# POWER.net
KiCad netlist of a schematic drawn in Altium Designer
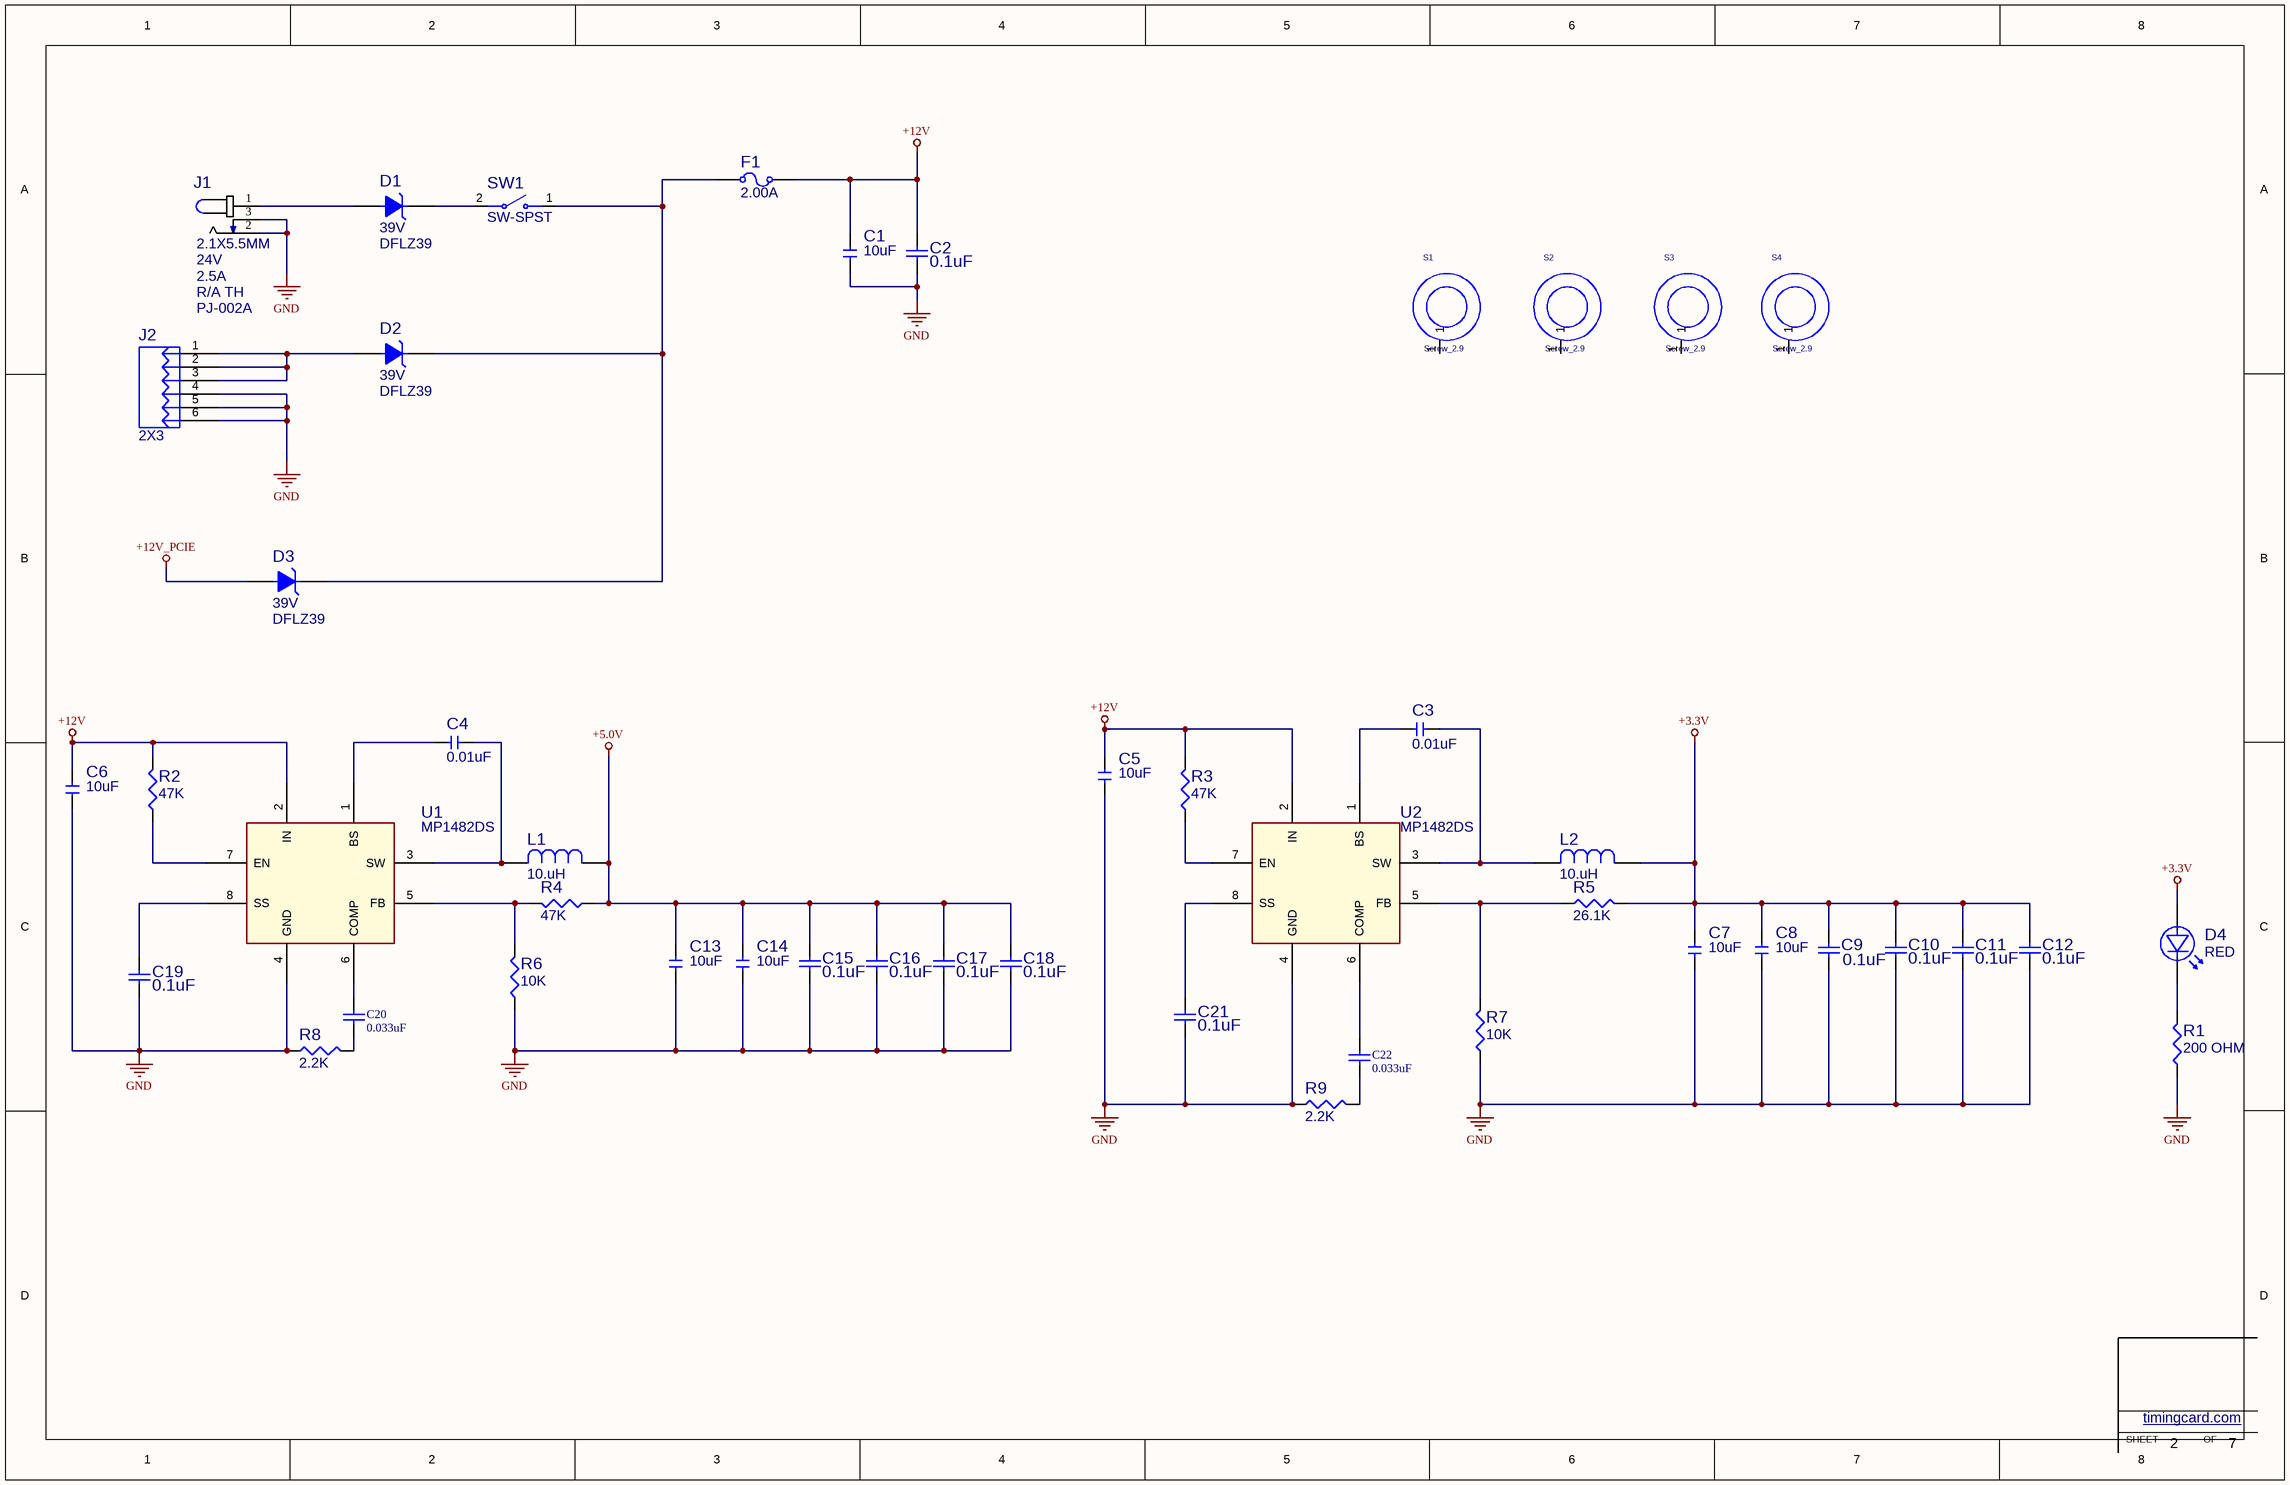
[diagram p0: POWER.SchDoc]

(export (version "E")
  (design (tool "Eeschema 10.0.6"))
  (components
    (comp (ref "C1")
      (value "10uF")
      (footprint "CAPC2012X14N")
      (description "CAP, CER, 10.UF, 25V, 10%, X5R, 0805")
      (fields
        (field (name "MFG PART NUM") "TMK212BBJ106KG-T")
        (field (name "VALENTIUM PART NUM") "<VALENTIUM>")
      )
      (libsource (lib "Capacitors") (part "CAP_0805_10UF_25V"))
    )
    (comp (ref "C2")
      (value "0.1uF")
      (footprint "CAPC1608X87X45ML20T05")
      (description "C0603X104K5RACAUTO")
      (fields (field (name "MANUFACTURER") "Kemet"))
      (libsource (lib "Altium Content Vault") (part "CAP"))
    )
    (comp (ref "C3")
      (value "0.01uF")
      (footprint "CAPC1608X10N")
      (description "CAP, CER, 0.01UF, 50V, 10%, X7R, 0603")
      (fields
        (field (name "MFG PART NUM") "C0603C103K5RACTU")
        (field (name "VALENTIUM PART NUM") "<VALENTIUM>")
      )
      (libsource (lib "Capacitors") (part "CAP_0603_0.01UF_50V"))
    )
    (comp (ref "C4")
      (value "0.01uF")
      (footprint "CAPC1608X10N")
      (description "CAP, CER, 0.01UF, 50V, 10%, X7R, 0603")
      (fields
        (field (name "MFG PART NUM") "C0603C103K5RACTU")
        (field (name "VALENTIUM PART NUM") "<VALENTIUM>")
      )
      (libsource (lib "Capacitors") (part "CAP_0603_0.01UF_50V"))
    )
    (comp (ref "C5")
      (value "10uF")
      (footprint "CAPC2012X14N")
      (description "CAP, CER, 10.UF, 25V, 10%, X5R, 0805")
      (fields
        (field (name "MFG PART NUM") "TMK212BBJ106KG-T")
        (field (name "VALENTIUM PART NUM") "<VALENTIUM>")
      )
      (libsource (lib "Capacitors") (part "CAP_0805_10UF_25V"))
    )
    (comp (ref "C6")
      (value "10uF")
      (footprint "CAPC2012X14N")
      (description "CAP, CER, 10.UF, 25V, 10%, X5R, 0805")
      (fields
        (field (name "MFG PART NUM") "TMK212BBJ106KG-T")
        (field (name "VALENTIUM PART NUM") "<VALENTIUM>")
      )
      (libsource (lib "Capacitors") (part "CAP_0805_10UF_25V"))
    )
    (comp (ref "C7")
      (value "10uF")
      (footprint "CAPC2012X14N")
      (description "CAP, CER, 10.UF, 25V, 10%, X5R, 0805")
      (fields
        (field (name "MFG PART NUM") "TMK212BBJ106KG-T")
        (field (name "VALENTIUM PART NUM") "<VALENTIUM>")
      )
      (libsource (lib "Capacitors") (part "CAP_0805_10UF_25V"))
    )
    (comp (ref "C8")
      (value "10uF")
      (footprint "CAPC2012X14N")
      (description "CAP, CER, 10.UF, 25V, 10%, X5R, 0805")
      (fields
        (field (name "MFG PART NUM") "TMK212BBJ106KG-T")
        (field (name "VALENTIUM PART NUM") "<VALENTIUM>")
      )
      (libsource (lib "Capacitors") (part "CAP_0805_10UF_25V"))
    )
    (comp (ref "C9")
      (value "0.1uF")
      (footprint "CAPC1608X87X45ML20T05")
      (description "C0603X104K5RACAUTO")
      (fields (field (name "MANUFACTURER") "Kemet"))
      (libsource (lib "Altium Content Vault") (part "CAP"))
    )
    (comp (ref "C10")
      (value "0.1uF")
      (footprint "CAPC1608X87X45ML20T05")
      (description "C0603X104K5RACAUTO")
      (fields (field (name "MANUFACTURER") "Kemet"))
      (libsource (lib "Altium Content Vault") (part "CAP"))
    )
    (comp (ref "C11")
      (value "0.1uF")
      (footprint "CAPC1608X87X45ML20T05")
      (description "C0603X104K5RACAUTO")
      (fields (field (name "MANUFACTURER") "Kemet"))
      (libsource (lib "Altium Content Vault") (part "CAP"))
    )
    (comp (ref "C12")
      (value "0.1uF")
      (footprint "CAPC1608X87X45ML20T05")
      (description "C0603X104K5RACAUTO")
      (fields (field (name "MANUFACTURER") "Kemet"))
      (libsource (lib "Altium Content Vault") (part "CAP"))
    )
    (comp (ref "C13")
      (value "10uF")
      (footprint "CAPC2012X14N")
      (description "CAP, CER, 10.UF, 25V, 10%, X5R, 0805")
      (fields
        (field (name "MFG PART NUM") "TMK212BBJ106KG-T")
        (field (name "VALENTIUM PART NUM") "<VALENTIUM>")
      )
      (libsource (lib "Capacitors") (part "CAP_0805_10UF_25V"))
    )
    (comp (ref "C14")
      (value "10uF")
      (footprint "CAPC2012X14N")
      (description "CAP, CER, 10.UF, 25V, 10%, X5R, 0805")
      (fields
        (field (name "MFG PART NUM") "TMK212BBJ106KG-T")
        (field (name "VALENTIUM PART NUM") "<VALENTIUM>")
      )
      (libsource (lib "Capacitors") (part "CAP_0805_10UF_25V"))
    )
    (comp (ref "C15")
      (value "0.1uF")
      (footprint "CAPC1608X87X45ML20T05")
      (description "C0603X104K5RACAUTO")
      (fields (field (name "MANUFACTURER") "Kemet"))
      (libsource (lib "Altium Content Vault") (part "CAP"))
    )
    (comp (ref "C16")
      (value "0.1uF")
      (footprint "CAPC1608X87X45ML20T05")
      (description "C0603X104K5RACAUTO")
      (fields (field (name "MANUFACTURER") "Kemet"))
      (libsource (lib "Altium Content Vault") (part "CAP"))
    )
    (comp (ref "C17")
      (value "0.1uF")
      (footprint "CAPC1608X87X45ML20T05")
      (description "C0603X104K5RACAUTO")
      (fields (field (name "MANUFACTURER") "Kemet"))
      (libsource (lib "Altium Content Vault") (part "CAP"))
    )
    (comp (ref "C18")
      (value "0.1uF")
      (footprint "CAPC1608X87X45ML20T05")
      (description "C0603X104K5RACAUTO")
      (fields (field (name "MANUFACTURER") "Kemet"))
      (libsource (lib "Altium Content Vault") (part "CAP"))
    )
    (comp (ref "C19")
      (value "0.1uF")
      (footprint "CAPC1608X87X45ML20T05")
      (description "C0603X104K5RACAUTO")
      (fields (field (name "MANUFACTURER") "Kemet"))
      (libsource (lib "Altium Content Vault") (part "CAP"))
    )
    (comp (ref "C20")
      (value "0.033uF")
      (footprint "CAPC1608X90X35NL10T15")
      (description "GCM188R71H333KA55D")
      (fields (field (name "MANUFACTURER") "Murata"))
      (libsource (lib "Altium Content Vault") (part "CAP"))
    )
    (comp (ref "C21")
      (value "0.1uF")
      (footprint "CAPC1608X87X45ML20T05")
      (description "C0603X104K5RACAUTO")
      (fields (field (name "MANUFACTURER") "Kemet"))
      (libsource (lib "Altium Content Vault") (part "CAP"))
    )
    (comp (ref "C22")
      (value "0.033uF")
      (footprint "CAPC1608X90X35NL10T15")
      (description "GCM188R71H333KA55D")
      (fields (field (name "MANUFACTURER") "Murata"))
      (libsource (lib "Altium Content Vault") (part "CAP"))
    )
    (comp (ref "D1")
      (value "DFLZ39")
      (footprint "SODFL370X135-2N")
      (description "DIO, ZENER, DFLZ39, 39V, 5%, 1W, SOD123FL")
      (fields
        (field (name "MFG PART NUM") "DFLZ39-TP")
        (field (name "P1") "39V")
        (field (name "VALENTIUM PART NUM") "<VALENTIUM>")
      )
      (libsource (lib "Passives") (part "DFLZ39"))
    )
    (comp (ref "D2")
      (value "DFLZ39")
      (footprint "SODFL370X135-2N")
      (description "DIO, ZENER, DFLZ39, 39V, 5%, 1W, SOD123FL")
      (fields
        (field (name "MFG PART NUM") "DFLZ39-TP")
        (field (name "P1") "39V")
        (field (name "VALENTIUM PART NUM") "<VALENTIUM>")
      )
      (libsource (lib "Passives") (part "DFLZ39"))
    )
    (comp (ref "D3")
      (value "DFLZ39")
      (footprint "SODFL370X135-2N")
      (description "DIO, ZENER, DFLZ39, 39V, 5%, 1W, SOD123FL")
      (fields
        (field (name "MFG PART NUM") "DFLZ39-TP")
        (field (name "P1") "39V")
        (field (name "VALENTIUM PART NUM") "<VALENTIUM>")
      )
      (libsource (lib "Passives") (part "DFLZ39"))
    )
    (comp (ref "D4")
      (value "RED")
      (footprint "DIOM1608X06N")
      (description "LED, RED, SML-LX0603, 635NM, 2V, 20MA, 0603")
      (fields
        (field (name "MFG PART NUM") "SML-LX0603IW-TR")
        (field (name "VALENTIUM PART NUM") "<VALENTIUM>")
      )
      (libsource (lib "Passives") (part "SMTLED_RED_0603_SML"))
    )
    (comp (ref "F1")
      (value "2.00A")
      (footprint "FUSM1608X60N")
      (description "FUSE SLOW 2.00A 32V M 0603")
      (fields (field (name "MFG PART NUM") "SF-0603S200-2") (field (name "VALENTIUM PART NUM") "<VALENTIUM>"))
      (libsource (lib "Passives") (part "FUSE_0603_2.00A"))
    )
    (comp (ref "J1")
      (value "PJ-002A")
      (footprint "CUI_PJ-002A")
      (description "CONN, JACK, PJ-002A, 2.1X5.5MM, 24V 2.5A, R/A TH, SPST-NC")
      (fields
        (field (name "VALENTIUM PART NUM") "<VALENTIUM>")
        (field (name "P1") "2.1X5.5MM")
        (field (name "P2") "24V")
        (field (name "P3") "2.5A")
        (field (name "SIZE") "R/A TH")
      )
      (libsource (lib "Connectors") (part "PJ-002A"))
    )
    (comp (ref "J2")
      (value "2X3")
      (footprint "39-30-1060")
      (description "CONN, HDR, 2X3, R/A, 4.2MM, TH, MINI-FIT JR")
      (fields (field (name "MFG PART NUM") "105314-1206") (field (name "VALENTIUM PART NUM") "<VALENTIUM>"))
      (libsource (lib "Connectors") (part "39-30-1060"))
    )
    (comp (ref "L1")
      (value "10.uH")
      (footprint "IND_PM124SH")
      (description "IND, PWR, 10.uH, 20%, 4A, 0.04DCR, 12.5X12.5MM, SHLD")
      (fields
        (field (name "MFG PART NUM") "PM124SH-100M-RC")
        (field (name "VALENTIUM PART NUM") "<VALENTIUM>")
      )
      (libsource (lib "Passives") (part "PM124SH-100M-RC"))
    )
    (comp (ref "L2")
      (value "10.uH")
      (footprint "IND_PM124SH")
      (description "IND, PWR, 10.uH, 20%, 4A, 0.04DCR, 12.5X12.5MM, SHLD")
      (fields
        (field (name "MFG PART NUM") "PM124SH-100M-RC")
        (field (name "VALENTIUM PART NUM") "<VALENTIUM>")
      )
      (libsource (lib "Passives") (part "PM124SH-100M-RC"))
    )
    (comp (ref "R1")
      (value "200 OHM")
      (footprint "RESC1608X50N")
      (description "RES, 200 OHM, 1%, 1/10W, TF, 0603")
      (fields (field (name "MFG PART NUM") "ERJ-3EKF2000V") (field (name "VELENTIUM PART NUM") "<VELENTIUM>"))
      (libsource (lib "Resistors") (part "RES_0603_200"))
    )
    (comp (ref "R2")
      (value "47K")
      (footprint "RESC1608X50N")
      (description "RES, 47K, 1%, 1/10W, TF, 0603")
      (fields (field (name "MFG PART NUM") "ERJ-3EKF4702V") (field (name "VELENTIUM PART NUM") "<VELENTIUM>"))
      (libsource (lib "Resistors") (part "RES_0603_47K"))
    )
    (comp (ref "R3")
      (value "47K")
      (footprint "RESC1608X50N")
      (description "RES, 47K, 1%, 1/10W, TF, 0603")
      (fields (field (name "MFG PART NUM") "ERJ-3EKF4702V") (field (name "VELENTIUM PART NUM") "<VELENTIUM>"))
      (libsource (lib "Resistors") (part "RES_0603_47K"))
    )
    (comp (ref "R4")
      (value "47K")
      (footprint "RESC1608X50N")
      (description "RES, 47K, 1%, 1/10W, TF, 0603")
      (fields (field (name "MFG PART NUM") "ERJ-3EKF4702V") (field (name "VELENTIUM PART NUM") "<VELENTIUM>"))
      (libsource (lib "Resistors") (part "RES_0603_47K"))
    )
    (comp (ref "R5")
      (value "26.1K")
      (footprint "RESC1608X50N")
      (description "RES, 26.1K, 1%, 1/10W, TF, 0603")
      (fields (field (name "MFG PART NUM") "ERJ-3EKF2612V") (field (name "VELENTIUM PART NUM") "<VELENTIUM>"))
      (libsource (lib "Resistors") (part "RES_0603_26.1K"))
    )
    (comp (ref "R6")
      (value "10K")
      (footprint "RESC1608X50N")
      (description "RES, 10K, 1%, 1/10W, TF, 0603")
      (fields (field (name "MFG PART NUM") "ERJ-3EKF1002V") (field (name "VELENTIUM PART NUM") "<VELENTIUM>"))
      (libsource (lib "Resistors") (part "RES_0603_10K"))
    )
    (comp (ref "R7")
      (value "10K")
      (footprint "RESC1608X50N")
      (description "RES, 10K, 1%, 1/10W, TF, 0603")
      (fields (field (name "MFG PART NUM") "ERJ-3EKF1002V") (field (name "VELENTIUM PART NUM") "<VELENTIUM>"))
      (libsource (lib "Resistors") (part "RES_0603_10K"))
    )
    (comp (ref "R8")
      (value "2.2K")
      (footprint "RESC1608X50N")
      (description "RES, 2.2K, 1%, 1/10W, TF, 0603")
      (fields (field (name "MFG PART NUM") "ERJ-3EKF2201V") (field (name "VELENTIUM PART NUM") "<VELENTIUM>"))
      (libsource (lib "Resistors") (part "RES_0603_2.2K"))
    )
    (comp (ref "R9")
      (value "2.2K")
      (footprint "RESC1608X50N")
      (description "RES, 2.2K, 1%, 1/10W, TF, 0603")
      (fields (field (name "MFG PART NUM") "ERJ-3EKF2201V") (field (name "VELENTIUM PART NUM") "<VELENTIUM>"))
      (libsource (lib "Resistors") (part "RES_0603_2.2K"))
    )
    (comp (ref "S1")
      (value "Screw_2.9")
      (footprint "MH_250H125")
      (description "FH140 Screw,Diameter 2.9mm")
      (fields (field (name "PART NUMBER") "454") (field (name "MANUFACTURER") "NA"))
      (libsource (lib "AX7103_AD_Schematics") (part "screw_0"))
    )
    (comp (ref "S2")
      (value "Screw_2.9")
      (footprint "MH_250H125")
      (description "FH140 Screw,Diameter 2.9mm")
      (fields (field (name "PART NUMBER") "454") (field (name "MANUFACTURER") "NA"))
      (libsource (lib "AX7103_AD_Schematics") (part "screw_0"))
    )
    (comp (ref "S3")
      (value "Screw_2.9")
      (footprint "MH_250H125")
      (description "FH140 Screw,Diameter 2.9mm")
      (fields (field (name "PART NUMBER") "454") (field (name "MANUFACTURER") "NA"))
      (libsource (lib "AX7103_AD_Schematics") (part "screw_0"))
    )
    (comp (ref "S4")
      (value "Screw_2.9")
      (footprint "MH_250H125")
      (description "FH140 Screw,Diameter 2.9mm")
      (fields (field (name "PART NUMBER") "454") (field (name "MANUFACTURER") "NA"))
      (libsource (lib "AX7103_AD_Schematics") (part "screw_0"))
    )
    (comp (ref "SW1")
      (value "SW-SPST")
      (footprint "L101011MS02Q")
      (description "SW, SPST, 250V, 2A, SLIDE, ON-OFF, TH")
      (fields (field (name "MFG PART NUM") "L101011MS02Q") (field (name "VALENTIUM PART NUM") "<VALENTIUM>"))
      (libsource (lib "Miscellaneous") (part "L101011MS02Q"))
    )
    (comp (ref "U1")
      (value "MP1482DS")
      (footprint "SOIC127P600X175-8N")
      (description "IC, DC/DC, MP1482DS, >4.75VIN, 0.923-15V OUT, SOIC8")
      (fields (field (name "MFG PART NUM") "MP1482DS-LF") (field (name "VELENTIUM PART NUM") "<V PART NUM>"))
      (libsource (lib "IntegratedCircuits") (part "MP1482DS"))
    )
    (comp (ref "U2")
      (value "MP1482DS")
      (footprint "SOIC127P600X175-8N")
      (description "IC, DC/DC, MP1482DS, >4.75VIN, 0.923-15V OUT, SOIC8")
      (fields (field (name "MFG PART NUM") "MP1482DS-LF") (field (name "VELENTIUM PART NUM") "<V PART NUM>"))
      (libsource (lib "IntegratedCircuits") (part "MP1482DS"))
    )
  )
  (nets
    (net (code "1") (name "+3.3V") (class "Default")
      (node (ref "C10") (pin "2") (pinfunction "2_2") (pintype "passive"))
      (node (ref "C11") (pin "2") (pinfunction "2_2") (pintype "passive"))
      (node (ref "C12") (pin "2") (pinfunction "2_2") (pintype "passive"))
      (node (ref "C7") (pin "1") (pinfunction "1_1") (pintype "passive"))
      (node (ref "C8") (pin "1") (pinfunction "1_1") (pintype "passive"))
      (node (ref "C9") (pin "2") (pinfunction "2_2") (pintype "passive"))
      (node (ref "D4") (pin "2") (pinfunction "A_2") (pintype "passive"))
      (node (ref "L2") (pin "1") (pintype "passive"))
      (node (ref "R5") (pin "2") (pinfunction "2_2") (pintype "passive"))
    )
    (net (code "2") (name "+5.0V") (class "Default")
      (node (ref "C13") (pin "1") (pinfunction "1_1") (pintype "passive"))
      (node (ref "C14") (pin "1") (pinfunction "1_1") (pintype "passive"))
      (node (ref "C15") (pin "2") (pinfunction "2_2") (pintype "passive"))
      (node (ref "C16") (pin "2") (pinfunction "2_2") (pintype "passive"))
      (node (ref "C17") (pin "2") (pinfunction "2_2") (pintype "passive"))
      (node (ref "C18") (pin "2") (pinfunction "2_2") (pintype "passive"))
      (node (ref "L1") (pin "1") (pintype "passive"))
      (node (ref "R4") (pin "1") (pinfunction "1_1") (pintype "passive"))
    )
    (net (code "3") (name "+12V") (class "Default")
      (node (ref "C1") (pin "1") (pinfunction "1_1") (pintype "passive"))
      (node (ref "C2") (pin "2") (pinfunction "2_2") (pintype "passive"))
      (node (ref "C5") (pin "1") (pinfunction "1_1") (pintype "passive"))
      (node (ref "C6") (pin "1") (pinfunction "1_1") (pintype "passive"))
      (node (ref "F1") (pin "2") (pinfunction "2_2") (pintype "passive"))
      (node (ref "R2") (pin "2") (pinfunction "2_2") (pintype "passive"))
      (node (ref "R3") (pin "2") (pinfunction "2_2") (pintype "passive"))
      (node (ref "U1") (pin "2") (pinfunction "IN_2") (pintype "passive"))
      (node (ref "U2") (pin "2") (pinfunction "IN_2") (pintype "passive"))
    )
    (net (code "4") (name "+12V_PCIE") (class "Default")
      (node (ref "D3") (pin "2") (pinfunction "A_2") (pintype "passive"))
    )
    (net (code "5") (name "GND") (class "Default")
      (node (ref "C1") (pin "2") (pinfunction "2_2") (pintype "passive"))
      (node (ref "C10") (pin "1") (pinfunction "1_1") (pintype "passive"))
      (node (ref "C11") (pin "1") (pinfunction "1_1") (pintype "passive"))
      (node (ref "C12") (pin "1") (pinfunction "1_1") (pintype "passive"))
      (node (ref "C13") (pin "2") (pinfunction "2_2") (pintype "passive"))
      (node (ref "C14") (pin "2") (pinfunction "2_2") (pintype "passive"))
      (node (ref "C15") (pin "1") (pinfunction "1_1") (pintype "passive"))
      (node (ref "C16") (pin "1") (pinfunction "1_1") (pintype "passive"))
      (node (ref "C17") (pin "1") (pinfunction "1_1") (pintype "passive"))
      (node (ref "C18") (pin "1") (pinfunction "1_1") (pintype "passive"))
      (node (ref "C19") (pin "1") (pinfunction "1_1") (pintype "passive"))
      (node (ref "C2") (pin "1") (pinfunction "1_1") (pintype "passive"))
      (node (ref "C21") (pin "1") (pinfunction "1_1") (pintype "passive"))
      (node (ref "C5") (pin "2") (pinfunction "2_2") (pintype "passive"))
      (node (ref "C6") (pin "2") (pinfunction "2_2") (pintype "passive"))
      (node (ref "C7") (pin "2") (pinfunction "2_2") (pintype "passive"))
      (node (ref "C8") (pin "2") (pinfunction "2_2") (pintype "passive"))
      (node (ref "C9") (pin "1") (pinfunction "1_1") (pintype "passive"))
      (node (ref "J1") (pin "2") (pinfunction "2_2") (pintype "passive"))
      (node (ref "J1") (pin "3") (pinfunction "3_3") (pintype "passive"))
      (node (ref "J2") (pin "4") (pintype "passive"))
      (node (ref "J2") (pin "5") (pintype "passive"))
      (node (ref "J2") (pin "6") (pintype "passive"))
      (node (ref "R1") (pin "1") (pinfunction "1_1") (pintype "passive"))
      (node (ref "R6") (pin "1") (pinfunction "1_1") (pintype "passive"))
      (node (ref "R7") (pin "1") (pinfunction "1_1") (pintype "passive"))
      (node (ref "R8") (pin "1") (pinfunction "1_1") (pintype "passive"))
      (node (ref "R9") (pin "1") (pinfunction "1_1") (pintype "passive"))
      (node (ref "U1") (pin "4") (pinfunction "GND_4") (pintype "passive"))
      (node (ref "U2") (pin "4") (pinfunction "GND_4") (pintype "passive"))
    )
    (net (code "6") (name "Net-(C20-Pad1)") (class "Default")
      (node (ref "C20") (pin "1") (pinfunction "1_1") (pintype "passive"))
      (node (ref "R8") (pin "2") (pinfunction "2_2") (pintype "passive"))
    )
    (net (code "7") (name "Net-(C22-Pad1)") (class "Default")
      (node (ref "C22") (pin "1") (pinfunction "1_1") (pintype "passive"))
      (node (ref "R9") (pin "2") (pinfunction "2_2") (pintype "passive"))
    )
    (net (code "8") (name "Net-(D1-A)") (class "Default")
      (node (ref "D1") (pin "2") (pinfunction "A_2") (pintype "passive"))
      (node (ref "J1") (pin "1") (pinfunction "1_1") (pintype "passive"))
    )
    (net (code "9") (name "Net-(D1-C)") (class "Default")
      (node (ref "D1") (pin "1") (pinfunction "C_1") (pintype "passive"))
      (node (ref "SW1") (pin "2") (pintype "passive"))
    )
    (net (code "10") (name "Net-(D2-A)") (class "Default")
      (node (ref "D2") (pin "2") (pinfunction "A_2") (pintype "passive"))
      (node (ref "J2") (pin "1") (pintype "passive"))
      (node (ref "J2") (pin "2") (pintype "passive"))
      (node (ref "J2") (pin "3") (pintype "passive"))
    )
    (net (code "11") (name "Net-(D2-C)") (class "Default")
      (node (ref "D2") (pin "1") (pinfunction "C_1") (pintype "passive"))
      (node (ref "D3") (pin "1") (pinfunction "C_1") (pintype "passive"))
      (node (ref "F1") (pin "1") (pinfunction "1_1") (pintype "passive"))
      (node (ref "SW1") (pin "1") (pintype "passive"))
    )
    (net (code "12") (name "Net-(D4-K)") (class "Default")
      (node (ref "D4") (pin "1") (pinfunction "K_1") (pintype "passive"))
      (node (ref "R1") (pin "2") (pinfunction "2_2") (pintype "passive"))
    )
    (net (code "13") (name "Net-(U1-BS)") (class "Default")
      (node (ref "C4") (pin "1") (pinfunction "1_1") (pintype "passive"))
      (node (ref "U1") (pin "1") (pinfunction "BS_1") (pintype "passive"))
    )
    (net (code "14") (name "Net-(U1-COMP)") (class "Default")
      (node (ref "C20") (pin "2") (pinfunction "2_2") (pintype "passive"))
      (node (ref "U1") (pin "6") (pinfunction "COMP_6") (pintype "passive"))
    )
    (net (code "15") (name "Net-(U1-EN)") (class "Default")
      (node (ref "R2") (pin "1") (pinfunction "1_1") (pintype "passive"))
      (node (ref "U1") (pin "7") (pinfunction "EN_7") (pintype "passive"))
    )
    (net (code "16") (name "Net-(U1-FB)") (class "Default")
      (node (ref "R4") (pin "2") (pinfunction "2_2") (pintype "passive"))
      (node (ref "R6") (pin "2") (pinfunction "2_2") (pintype "passive"))
      (node (ref "U1") (pin "5") (pinfunction "FB_5") (pintype "passive"))
    )
    (net (code "17") (name "Net-(U1-SS)") (class "Default")
      (node (ref "C19") (pin "2") (pinfunction "2_2") (pintype "passive"))
      (node (ref "U1") (pin "8") (pinfunction "SS_8") (pintype "passive"))
    )
    (net (code "18") (name "Net-(U1-SW)") (class "Default")
      (node (ref "C4") (pin "2") (pinfunction "2_2") (pintype "passive"))
      (node (ref "L1") (pin "2") (pintype "passive"))
      (node (ref "U1") (pin "3") (pinfunction "SW_3") (pintype "passive"))
    )
    (net (code "19") (name "Net-(U2-BS)") (class "Default")
      (node (ref "C3") (pin "1") (pinfunction "1_1") (pintype "passive"))
      (node (ref "U2") (pin "1") (pinfunction "BS_1") (pintype "passive"))
    )
    (net (code "20") (name "Net-(U2-COMP)") (class "Default")
      (node (ref "C22") (pin "2") (pinfunction "2_2") (pintype "passive"))
      (node (ref "U2") (pin "6") (pinfunction "COMP_6") (pintype "passive"))
    )
    (net (code "21") (name "Net-(U2-EN)") (class "Default")
      (node (ref "R3") (pin "1") (pinfunction "1_1") (pintype "passive"))
      (node (ref "U2") (pin "7") (pinfunction "EN_7") (pintype "passive"))
    )
    (net (code "22") (name "Net-(U2-FB)") (class "Default")
      (node (ref "R5") (pin "1") (pinfunction "1_1") (pintype "passive"))
      (node (ref "R7") (pin "2") (pinfunction "2_2") (pintype "passive"))
      (node (ref "U2") (pin "5") (pinfunction "FB_5") (pintype "passive"))
    )
    (net (code "23") (name "Net-(U2-SS)") (class "Default")
      (node (ref "C21") (pin "2") (pinfunction "2_2") (pintype "passive"))
      (node (ref "U2") (pin "8") (pinfunction "SS_8") (pintype "passive"))
    )
    (net (code "24") (name "Net-(U2-SW)") (class "Default")
      (node (ref "C3") (pin "2") (pinfunction "2_2") (pintype "passive"))
      (node (ref "L2") (pin "2") (pintype "passive"))
      (node (ref "U2") (pin "3") (pinfunction "SW_3") (pintype "passive"))
    )
    (net (code "25") (name "unconnected-(S1-Pad1)") (class "Default")
      (node (ref "S1") (pin "1") (pinfunction "1_1") (pintype "passive"))
    )
    (net (code "26") (name "unconnected-(S2-Pad1)") (class "Default")
      (node (ref "S2") (pin "1") (pinfunction "1_1") (pintype "passive"))
    )
    (net (code "27") (name "unconnected-(S3-Pad1)") (class "Default")
      (node (ref "S3") (pin "1") (pinfunction "1_1") (pintype "passive"))
    )
    (net (code "28") (name "unconnected-(S4-Pad1)") (class "Default")
      (node (ref "S4") (pin "1") (pinfunction "1_1") (pintype "passive"))
    )
  )
)
